# Buffer.net
KiCad netlist of a schematic drawn in Altium Designer
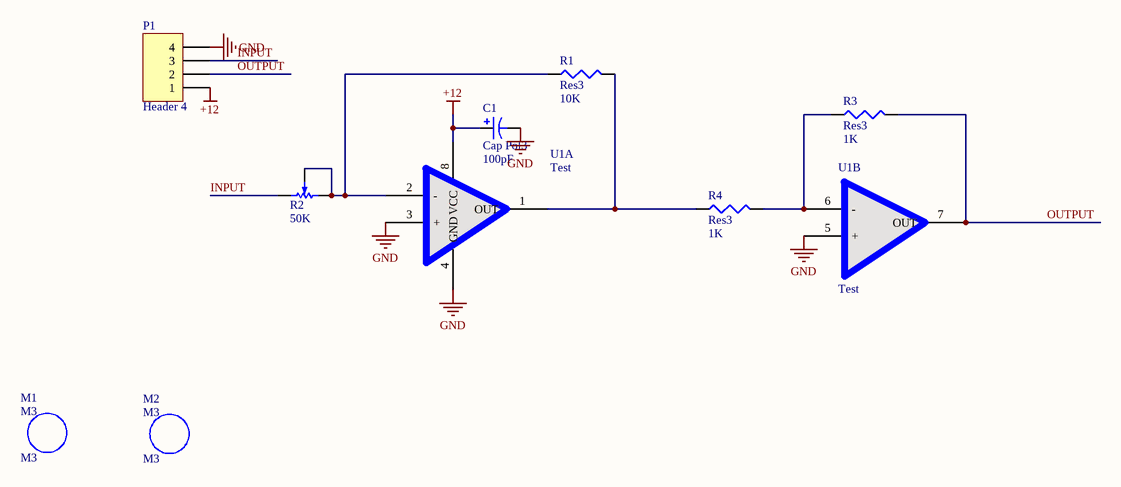
[diagram p0: Buffer.SchDoc]

(export (version "E")
  (design (tool "Eeschema 10.0.6"))
  (components
    (comp (ref "C1")
      (value "Cap Pol3")
      (footprint "1206")
      (description "Polarized Capacitor (Surface Mount)")
      (fields (field (name "ALTIUM_VALUE") "100pF") (field (name "PUBLISHER") "Altium Limited"))
      (libsource (lib "Miscellaneous Devices") (part "Cap Pol3"))
    )
    (comp (ref "M1") (value "M3") (footprint "M3 Mounting Hole") (libsource (lib "Buffer") (part "M3")))
    (comp (ref "M2") (value "M3") (footprint "M3 Mounting Hole") (libsource (lib "Buffer") (part "M3")))
    (comp (ref "P1")
      (value "Header 4")
      (footprint "HDR1X4")
      (description "Header, 4-Pin")
      (fields (field (name "PUBLISHER") "Altium Limited"))
      (libsource (lib "Miscellaneous Connectors") (part "Header 4"))
    )
    (comp (ref "R1")
      (value "Res3")
      (footprint "1206")
      (description "Resistor")
      (fields (field (name "ALTIUM_VALUE") "10K") (field (name "PUBLISHER") "Altium Limited"))
      (libsource (lib "Miscellaneous Devices") (part "Res3"))
    )
    (comp (ref "R2")
      (value "50K")
      (footprint "POT")
      (description "Square Trimming Potentiometer")
      (fields (field (name "PUBLISHER") "Altium Limited"))
      (libsource (lib "Miscellaneous Devices") (part "RPot SM"))
    )
    (comp (ref "R3")
      (value "Res3")
      (footprint "1206")
      (description "Resistor")
      (fields (field (name "ALTIUM_VALUE") "1K") (field (name "PUBLISHER") "Altium Limited"))
      (libsource (lib "Miscellaneous Devices") (part "Res3"))
    )
    (comp (ref "R4")
      (value "Res3")
      (footprint "1206")
      (description "Resistor")
      (fields (field (name "ALTIUM_VALUE") "1K") (field (name "PUBLISHER") "Altium Limited"))
      (libsource (lib "Miscellaneous Devices") (part "Res3"))
    )
    (comp (ref "U1") (value "Test") (footprint "SO8") (libsource (lib "Buffer") (part "Test")))
  )
  (nets
    (net (code "1") (name "+12") (class "Default")
      (node (ref "C1") (pin "1") (pinfunction "1_1") (pintype "passive"))
      (node (ref "P1") (pin "1") (pinfunction "1_1") (pintype "passive"))
      (node (ref "U1") (pin "8") (pinfunction "VCC_8") (pintype "passive"))
    )
    (net (code "2") (name "/INPUT") (class "Default")
      (node (ref "P1") (pin "3") (pinfunction "3_3") (pintype "passive"))
      (node (ref "R2") (pin "CW") (pinfunction "+_CW") (pintype "passive"))
    )
    (net (code "3") (name "/OUTPUT") (class "Default")
      (node (ref "P1") (pin "2") (pinfunction "2_2") (pintype "passive"))
      (node (ref "R3") (pin "2") (pinfunction "2_2") (pintype "passive"))
      (node (ref "U1") (pin "7") (pinfunction "OUT_7") (pintype "passive"))
    )
    (net (code "4") (name "GND") (class "Default")
      (node (ref "C1") (pin "2") (pinfunction "2_2") (pintype "passive"))
      (node (ref "P1") (pin "4") (pinfunction "4_4") (pintype "passive"))
      (node (ref "U1") (pin "3") (pinfunction "+_3") (pintype "passive"))
      (node (ref "U1") (pin "4") (pinfunction "GND_4") (pintype "passive"))
      (node (ref "U1") (pin "5") (pinfunction "+_5") (pintype "passive"))
    )
    (net (code "5") (name "Net-(R2--)") (class "Default")
      (node (ref "R1") (pin "1") (pinfunction "1_1") (pintype "passive"))
      (node (ref "R2") (pin "CCW") (pinfunction "-_CCW") (pintype "passive"))
      (node (ref "R2") (pin "W") (pinfunction "W_W") (pintype "passive"))
      (node (ref "U1") (pin "2") (pinfunction "-_2") (pintype "passive"))
    )
    (net (code "6") (name "Net-(U1A-OUT)") (class "Default")
      (node (ref "R1") (pin "2") (pinfunction "2_2") (pintype "passive"))
      (node (ref "R4") (pin "1") (pinfunction "1_1") (pintype "passive"))
      (node (ref "U1") (pin "1") (pinfunction "OUT_1") (pintype "passive"))
    )
    (net (code "7") (name "Net-(U1B--)") (class "Default")
      (node (ref "R3") (pin "1") (pinfunction "1_1") (pintype "passive"))
      (node (ref "R4") (pin "2") (pinfunction "2_2") (pintype "passive"))
      (node (ref "U1") (pin "6") (pinfunction "-_6") (pintype "passive"))
    )
  )
)
